# trashotron-v1.net
KiCad netlist of a schematic drawn in EAGLE
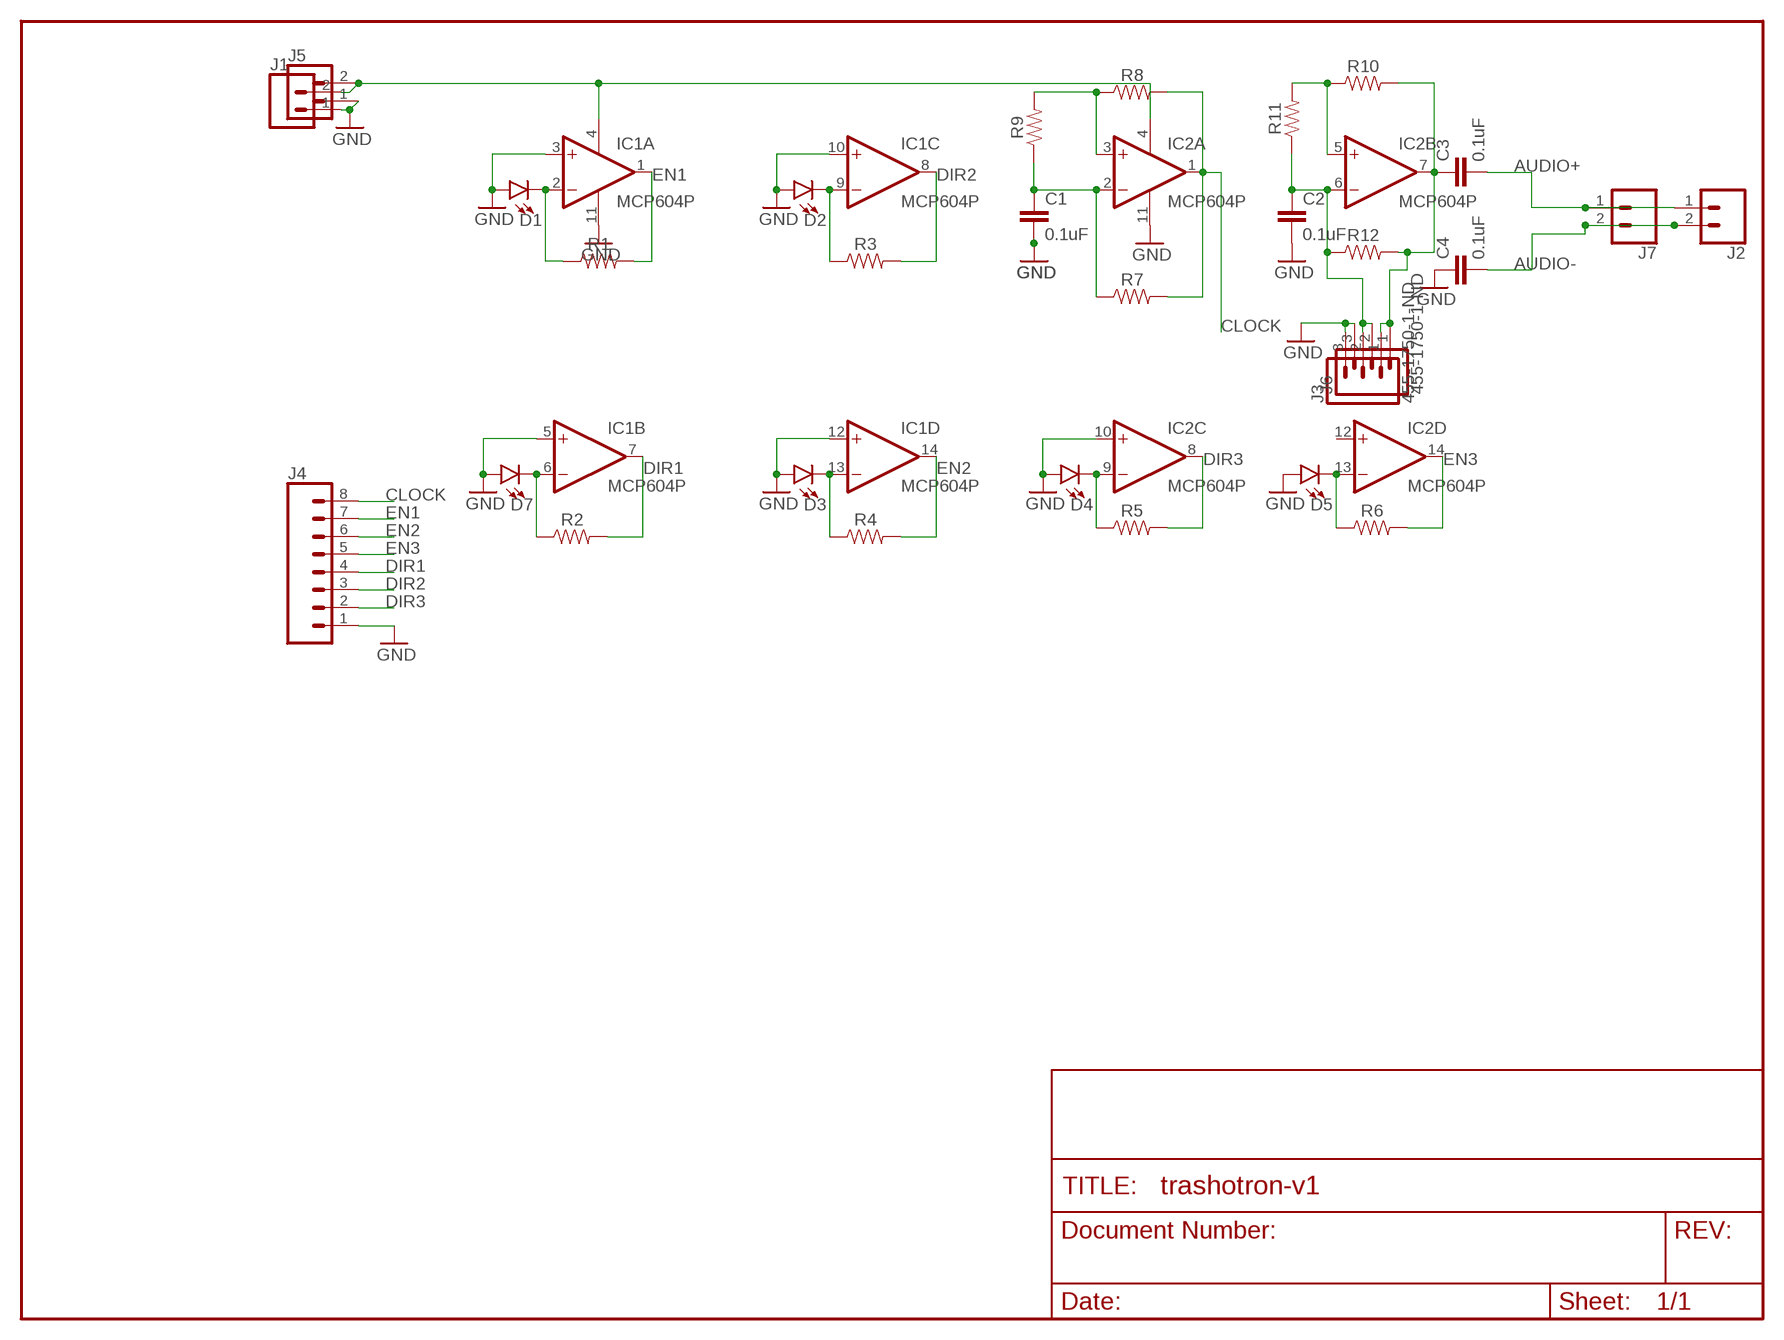
[diagram p0: schematic, sheet 1]

(export (version "E")
  (design (tool "Eeschema 10.0.6"))
  (components
    (comp (ref "C1")
      (value "0.1uF")
      (footprint "eagle-import:CAP-PTH-SMALL-KIT")
      (libsource (lib "eagle-import") (part "0.1UF-KIT-EZ-50V-20%"))
    )
    (comp (ref "C2")
      (value "0.1uF")
      (footprint "eagle-import:CAP-PTH-SMALL-KIT")
      (libsource (lib "eagle-import") (part "0.1UF-KIT-EZ-50V-20%"))
    )
    (comp (ref "C3")
      (value "0.1uF")
      (footprint "eagle-import:CAP-PTH-SMALL-KIT")
      (libsource (lib "eagle-import") (part "0.1UF-KIT-EZ-50V-20%"))
    )
    (comp (ref "C4")
      (value "0.1uF")
      (footprint "eagle-import:CAP-PTH-SMALL-KIT")
      (libsource (lib "eagle-import") (part "0.1UF-KIT-EZ-50V-20%"))
    )
    (comp (ref "D1")
      (value "LED3MM")
      (footprint "eagle-import:LED_3MM")
      (libsource (lib "eagle-import") (part "LED3MM"))
    )
    (comp (ref "D2")
      (value "LED3MM")
      (footprint "eagle-import:LED_3MM")
      (libsource (lib "eagle-import") (part "LED3MM"))
    )
    (comp (ref "D3")
      (value "LED3MM")
      (footprint "eagle-import:LED_3MM")
      (libsource (lib "eagle-import") (part "LED3MM"))
    )
    (comp (ref "D4")
      (value "LED3MM")
      (footprint "eagle-import:LED_3MM")
      (libsource (lib "eagle-import") (part "LED3MM"))
    )
    (comp (ref "D5")
      (value "LED3MM")
      (footprint "eagle-import:LED_3MM")
      (libsource (lib "eagle-import") (part "LED3MM"))
    )
    (comp (ref "D7")
      (value "LED3MM")
      (footprint "eagle-import:LED_3MM")
      (libsource (lib "eagle-import") (part "LED3MM"))
    )
    (comp (ref "IC1")
      (value "MCP604P")
      (footprint "eagle-import:DIL14")
      (libsource (lib "eagle-import") (part "MCP604P"))
    )
    (comp (ref "IC2")
      (value "MCP604P")
      (footprint "eagle-import:DIL14")
      (libsource (lib "eagle-import") (part "MCP604P"))
    )
    (comp (ref "J1")
      (value "CONN_02")
      (footprint "eagle-import:1X02")
      (libsource (lib "eagle-import") (part "CONN_02"))
    )
    (comp (ref "J2")
      (value "CONN_02")
      (footprint "eagle-import:1X02")
      (libsource (lib "eagle-import") (part "CONN_02"))
    )
    (comp (ref "J3")
      (value "455-1750-1-ND")
      (footprint "eagle-import:1X03")
      (libsource (lib "eagle-import") (part "CONN_03"))
    )
    (comp (ref "J4")
      (value "CONN_08\"")
      (footprint "eagle-import:1X08")
      (libsource (lib "eagle-import") (part "CONN_08{dblquote}"))
    )
    (comp (ref "J5")
      (value "CONN_02")
      (footprint "eagle-import:1X02")
      (libsource (lib "eagle-import") (part "CONN_02"))
    )
    (comp (ref "J6")
      (value "455-1750-1-ND")
      (footprint "eagle-import:1X03")
      (libsource (lib "eagle-import") (part "CONN_03"))
    )
    (comp (ref "J7")
      (value "CONN_02")
      (footprint "eagle-import:1X02")
      (libsource (lib "eagle-import") (part "CONN_02"))
    )
    (comp (ref "R1")
      (value "RESISTORAXIAL-0.3")
      (footprint "eagle-import:AXIAL-0.3")
      (libsource (lib "eagle-import") (part "RESISTORAXIAL-0.3"))
    )
    (comp (ref "R2")
      (value "RESISTORAXIAL-0.3")
      (footprint "eagle-import:AXIAL-0.3")
      (libsource (lib "eagle-import") (part "RESISTORAXIAL-0.3"))
    )
    (comp (ref "R3")
      (value "RESISTORAXIAL-0.3")
      (footprint "eagle-import:AXIAL-0.3")
      (libsource (lib "eagle-import") (part "RESISTORAXIAL-0.3"))
    )
    (comp (ref "R4")
      (value "RESISTORAXIAL-0.3")
      (footprint "eagle-import:AXIAL-0.3")
      (libsource (lib "eagle-import") (part "RESISTORAXIAL-0.3"))
    )
    (comp (ref "R5")
      (value "RESISTORAXIAL-0.3")
      (footprint "eagle-import:AXIAL-0.3")
      (libsource (lib "eagle-import") (part "RESISTORAXIAL-0.3"))
    )
    (comp (ref "R6")
      (value "RESISTORAXIAL-0.3")
      (footprint "eagle-import:AXIAL-0.3")
      (libsource (lib "eagle-import") (part "RESISTORAXIAL-0.3"))
    )
    (comp (ref "R7")
      (value "RESISTORAXIAL-0.3")
      (footprint "eagle-import:AXIAL-0.3")
      (libsource (lib "eagle-import") (part "RESISTORAXIAL-0.3"))
    )
    (comp (ref "R8")
      (value "RESISTORAXIAL-0.3")
      (footprint "eagle-import:AXIAL-0.3")
      (libsource (lib "eagle-import") (part "RESISTORAXIAL-0.3"))
    )
    (comp (ref "R9")
      (value "RESISTORAXIAL-0.3")
      (footprint "eagle-import:AXIAL-0.3")
      (libsource (lib "eagle-import") (part "RESISTORAXIAL-0.3"))
    )
    (comp (ref "R10")
      (value "RESISTORAXIAL-0.3")
      (footprint "eagle-import:AXIAL-0.3")
      (libsource (lib "eagle-import") (part "RESISTORAXIAL-0.3"))
    )
    (comp (ref "R11")
      (value "RESISTORAXIAL-0.3")
      (footprint "eagle-import:AXIAL-0.3")
      (libsource (lib "eagle-import") (part "RESISTORAXIAL-0.3"))
    )
    (comp (ref "R12")
      (value "RESISTORAXIAL-0.3")
      (footprint "eagle-import:AXIAL-0.3")
      (libsource (lib "eagle-import") (part "RESISTORAXIAL-0.3"))
    )
  )
  (nets
    (net (code "1") (name "/AUDIO+") (class "Default")
      (node (ref "C3") (pin "2") (pinfunction "2_2") (pintype "passive"))
      (node (ref "J2") (pin "1") (pinfunction "1_1") (pintype "passive"))
      (node (ref "J7") (pin "1") (pinfunction "1_1") (pintype "passive"))
    )
    (net (code "2") (name "/AUDIO-") (class "Default")
      (node (ref "C4") (pin "2") (pinfunction "2_2") (pintype "passive"))
      (node (ref "J2") (pin "2") (pinfunction "2_2") (pintype "passive"))
      (node (ref "J7") (pin "2") (pinfunction "2_2") (pintype "passive"))
    )
    (net (code "3") (name "/CLOCK") (class "Default")
      (node (ref "IC2") (pin "1") (pinfunction "OUT_1") (pintype "output"))
      (node (ref "J4") (pin "8") (pinfunction "8_8") (pintype "passive"))
      (node (ref "R7") (pin "P$2") (pinfunction "2_P$2") (pintype "passive"))
      (node (ref "R8") (pin "P$2") (pinfunction "2_P$2") (pintype "passive"))
    )
    (net (code "4") (name "/DIR1") (class "Default")
      (node (ref "IC1") (pin "7") (pinfunction "OUT_7") (pintype "output"))
      (node (ref "J4") (pin "4") (pinfunction "4_4") (pintype "passive"))
      (node (ref "R2") (pin "P$2") (pinfunction "2_P$2") (pintype "passive"))
    )
    (net (code "5") (name "/DIR2") (class "Default")
      (node (ref "IC1") (pin "8") (pinfunction "OUT_8") (pintype "output"))
      (node (ref "J4") (pin "3") (pinfunction "3_3") (pintype "passive"))
      (node (ref "R3") (pin "P$2") (pinfunction "2_P$2") (pintype "passive"))
    )
    (net (code "6") (name "/DIR3") (class "Default")
      (node (ref "IC2") (pin "8") (pinfunction "OUT_8") (pintype "output"))
      (node (ref "J4") (pin "2") (pinfunction "2_2") (pintype "passive"))
      (node (ref "R5") (pin "P$2") (pinfunction "2_P$2") (pintype "passive"))
    )
    (net (code "7") (name "/EN1") (class "Default")
      (node (ref "IC1") (pin "1") (pinfunction "OUT_1") (pintype "output"))
      (node (ref "J4") (pin "7") (pinfunction "7_7") (pintype "passive"))
      (node (ref "R1") (pin "P$2") (pinfunction "2_P$2") (pintype "passive"))
    )
    (net (code "8") (name "/EN2") (class "Default")
      (node (ref "IC1") (pin "14") (pinfunction "OUT_14") (pintype "output"))
      (node (ref "J4") (pin "6") (pinfunction "6_6") (pintype "passive"))
      (node (ref "R4") (pin "P$2") (pinfunction "2_P$2") (pintype "passive"))
    )
    (net (code "9") (name "/EN3") (class "Default")
      (node (ref "IC2") (pin "14") (pinfunction "OUT_14") (pintype "output"))
      (node (ref "J4") (pin "5") (pinfunction "5_5") (pintype "passive"))
      (node (ref "R6") (pin "P$2") (pinfunction "2_P$2") (pintype "passive"))
    )
    (net (code "10") (name "GND") (class "Default")
      (node (ref "C1") (pin "2") (pinfunction "2_2") (pintype "passive"))
      (node (ref "C2") (pin "2") (pinfunction "2_2") (pintype "passive"))
      (node (ref "C4") (pin "1") (pinfunction "1_1") (pintype "passive"))
      (node (ref "D1") (pin "A") (pinfunction "A_A") (pintype "passive"))
      (node (ref "D2") (pin "A") (pinfunction "A_A") (pintype "passive"))
      (node (ref "D3") (pin "A") (pinfunction "A_A") (pintype "passive"))
      (node (ref "D4") (pin "A") (pinfunction "A_A") (pintype "passive"))
      (node (ref "D5") (pin "A") (pinfunction "A_A") (pintype "passive"))
      (node (ref "D7") (pin "A") (pinfunction "A_A") (pintype "passive"))
      (node (ref "IC1") (pin "10") (pinfunction "+IN_10") (pintype "input"))
      (node (ref "IC1") (pin "11") (pinfunction "V-_11") (pintype "power_in"))
      (node (ref "IC1") (pin "12") (pinfunction "+IN_12") (pintype "input"))
      (node (ref "IC1") (pin "3") (pinfunction "+IN_3") (pintype "input"))
      (node (ref "IC1") (pin "5") (pinfunction "+IN_5") (pintype "input"))
      (node (ref "IC2") (pin "10") (pinfunction "+IN_10") (pintype "input"))
      (node (ref "IC2") (pin "11") (pinfunction "V-_11") (pintype "power_in"))
      (node (ref "J1") (pin "1") (pinfunction "1_1") (pintype "passive"))
      (node (ref "J3") (pin "3") (pinfunction "3_3") (pintype "passive"))
      (node (ref "J4") (pin "1") (pinfunction "1_1") (pintype "passive"))
      (node (ref "J5") (pin "1") (pinfunction "1_1") (pintype "passive"))
      (node (ref "J6") (pin "3") (pinfunction "3_3") (pintype "passive"))
    )
    (net (code "11") (name "Net-(D1-C)") (class "Default")
      (node (ref "D1") (pin "K") (pinfunction "C_K") (pintype "passive"))
      (node (ref "IC1") (pin "2") (pinfunction "-IN_2") (pintype "input"))
      (node (ref "R1") (pin "P$1") (pinfunction "1_P$1") (pintype "passive"))
    )
    (net (code "12") (name "Net-(D2-C)") (class "Default")
      (node (ref "D2") (pin "K") (pinfunction "C_K") (pintype "passive"))
      (node (ref "IC1") (pin "9") (pinfunction "-IN_9") (pintype "input"))
      (node (ref "R3") (pin "P$1") (pinfunction "1_P$1") (pintype "passive"))
    )
    (net (code "13") (name "Net-(D3-C)") (class "Default")
      (node (ref "D3") (pin "K") (pinfunction "C_K") (pintype "passive"))
      (node (ref "IC1") (pin "13") (pinfunction "-IN_13") (pintype "input"))
      (node (ref "R4") (pin "P$1") (pinfunction "1_P$1") (pintype "passive"))
    )
    (net (code "14") (name "Net-(D4-C)") (class "Default")
      (node (ref "D4") (pin "K") (pinfunction "C_K") (pintype "passive"))
      (node (ref "IC2") (pin "9") (pinfunction "-IN_9") (pintype "input"))
      (node (ref "R5") (pin "P$1") (pinfunction "1_P$1") (pintype "passive"))
    )
    (net (code "15") (name "Net-(D5-C)") (class "Default")
      (node (ref "D5") (pin "K") (pinfunction "C_K") (pintype "passive"))
      (node (ref "IC2") (pin "13") (pinfunction "-IN_13") (pintype "input"))
      (node (ref "R6") (pin "P$1") (pinfunction "1_P$1") (pintype "passive"))
    )
    (net (code "16") (name "Net-(D7-C)") (class "Default")
      (node (ref "D7") (pin "K") (pinfunction "C_K") (pintype "passive"))
      (node (ref "IC1") (pin "6") (pinfunction "-IN_6") (pintype "input"))
      (node (ref "R2") (pin "P$1") (pinfunction "1_P$1") (pintype "passive"))
    )
    (net (code "17") (name "Net-(IC1E-V+)") (class "Default")
      (node (ref "IC1") (pin "4") (pinfunction "V+_4") (pintype "power_in"))
      (node (ref "IC2") (pin "4") (pinfunction "V+_4") (pintype "power_in"))
      (node (ref "J1") (pin "2") (pinfunction "2_2") (pintype "passive"))
      (node (ref "J5") (pin "2") (pinfunction "2_2") (pintype "passive"))
    )
    (net (code "18") (name "Net-(IC2A-+IN)") (class "Default")
      (node (ref "IC2") (pin "3") (pinfunction "+IN_3") (pintype "input"))
      (node (ref "R8") (pin "P$1") (pinfunction "1_P$1") (pintype "passive"))
      (node (ref "R9") (pin "P$2") (pinfunction "2_P$2") (pintype "passive"))
    )
    (net (code "19") (name "Net-(IC2A--IN)") (class "Default")
      (node (ref "C1") (pin "1") (pinfunction "1_1") (pintype "passive"))
      (node (ref "IC2") (pin "2") (pinfunction "-IN_2") (pintype "input"))
      (node (ref "R7") (pin "P$1") (pinfunction "1_P$1") (pintype "passive"))
      (node (ref "R9") (pin "P$1") (pinfunction "1_P$1") (pintype "passive"))
    )
    (net (code "20") (name "Net-(IC2B-+IN)") (class "Default")
      (node (ref "IC2") (pin "5") (pinfunction "+IN_5") (pintype "input"))
      (node (ref "R10") (pin "P$1") (pinfunction "1_P$1") (pintype "passive"))
      (node (ref "R11") (pin "P$2") (pinfunction "2_P$2") (pintype "passive"))
    )
    (net (code "21") (name "Net-(IC2B--IN)") (class "Default")
      (node (ref "C2") (pin "1") (pinfunction "1_1") (pintype "passive"))
      (node (ref "IC2") (pin "6") (pinfunction "-IN_6") (pintype "input"))
      (node (ref "J3") (pin "2") (pinfunction "2_2") (pintype "passive"))
      (node (ref "J6") (pin "2") (pinfunction "2_2") (pintype "passive"))
      (node (ref "R11") (pin "P$1") (pinfunction "1_P$1") (pintype "passive"))
      (node (ref "R12") (pin "P$1") (pinfunction "1_P$1") (pintype "passive"))
    )
    (net (code "22") (name "Net-(IC2B-OUT)") (class "Default")
      (node (ref "C3") (pin "1") (pinfunction "1_1") (pintype "passive"))
      (node (ref "IC2") (pin "7") (pinfunction "OUT_7") (pintype "output"))
      (node (ref "J3") (pin "1") (pinfunction "1_1") (pintype "passive"))
      (node (ref "J6") (pin "1") (pinfunction "1_1") (pintype "passive"))
      (node (ref "R10") (pin "P$2") (pinfunction "2_P$2") (pintype "passive"))
      (node (ref "R12") (pin "P$2") (pinfunction "2_P$2") (pintype "passive"))
    )
    (net (code "23") (name "unconnected-(IC2D-+IN-Pad12)") (class "Default")
      (node (ref "IC2") (pin "12") (pinfunction "+IN_12") (pintype "input"))
    )
  )
)
